# sxbp-169.net
KiCad netlist of a schematic drawn in EAGLE
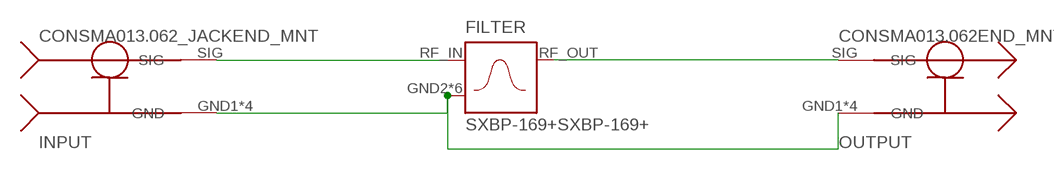
[diagram p0: schematic, sheet 1]

(export (version "E")
  (design (tool "Eeschema 10.0.6"))
  (components
    (comp (ref "FILTER")
      (value "SXBP-169+SXBP-169+")
      (footprint "eagle-import:HF1139")
      (libsource (lib "eagle-import") (part "SXBP-169+SXBP-169+"))
    )
    (comp (ref "INPUT")
      (value "CONSMA013.062_JACKEND_MNT")
      (footprint "eagle-import:SMA_EDGE_MNT")
      (libsource (lib "eagle-import") (part "CONSMA013.062_JACKEND_MNT"))
    )
    (comp (ref "OUTPUT")
      (value "CONSMA013.062END_MNT")
      (footprint "eagle-import:SMA_EDGE_MNT")
      (libsource (lib "eagle-import") (part "CONSMA013.062END_MNT"))
    )
  )
  (nets
    (net (code "1") (name "Net-(FILTER-GND_IN-PadGND2)") (class "Default")
      (node (ref "FILTER") (pin "GND2") (pinfunction "GND_IN_GND2") (pintype "bidirectional"))
      (node (ref "FILTER") (pin "GND3") (pinfunction "GND_IN_GND3") (pintype "bidirectional"))
      (node (ref "FILTER") (pin "GND4") (pinfunction "GND_IN_GND4") (pintype "bidirectional"))
      (node (ref "FILTER") (pin "GND5") (pinfunction "GND_IN_GND5") (pintype "bidirectional"))
      (node (ref "FILTER") (pin "GND6") (pinfunction "GND_IN_GND6") (pintype "bidirectional"))
      (node (ref "FILTER") (pin "GND7") (pinfunction "GND_IN_GND7") (pintype "bidirectional"))
      (node (ref "INPUT") (pin "GND1") (pinfunction "GND_GND1") (pintype "bidirectional"))
      (node (ref "INPUT") (pin "GND2") (pinfunction "GND_GND2") (pintype "bidirectional"))
      (node (ref "INPUT") (pin "GND3") (pinfunction "GND_GND3") (pintype "bidirectional"))
      (node (ref "INPUT") (pin "GND4") (pinfunction "GND_GND4") (pintype "bidirectional"))
      (node (ref "OUTPUT") (pin "GND1") (pinfunction "GND_GND1") (pintype "bidirectional"))
      (node (ref "OUTPUT") (pin "GND2") (pinfunction "GND_GND2") (pintype "bidirectional"))
      (node (ref "OUTPUT") (pin "GND3") (pinfunction "GND_GND3") (pintype "bidirectional"))
      (node (ref "OUTPUT") (pin "GND4") (pinfunction "GND_GND4") (pintype "bidirectional"))
    )
    (net (code "2") (name "Net-(FILTER-PadRF_IN)") (class "Default")
      (node (ref "FILTER") (pin "RF_IN") (pinfunction "RF_IN_RF_IN") (pintype "input"))
      (node (ref "INPUT") (pin "SIG") (pinfunction "SIG_SIG") (pintype "bidirectional"))
    )
    (net (code "3") (name "Net-(FILTER-PadRF_OUT)") (class "Default")
      (node (ref "FILTER") (pin "RF_OUT") (pinfunction "RF_OUT_RF_OUT") (pintype "output"))
      (node (ref "OUTPUT") (pin "SIG") (pinfunction "SIG_SIG") (pintype "bidirectional"))
    )
  )
)
